# blinky-sch-done.net
KiCad netlist of a schematic drawn in EAGLE
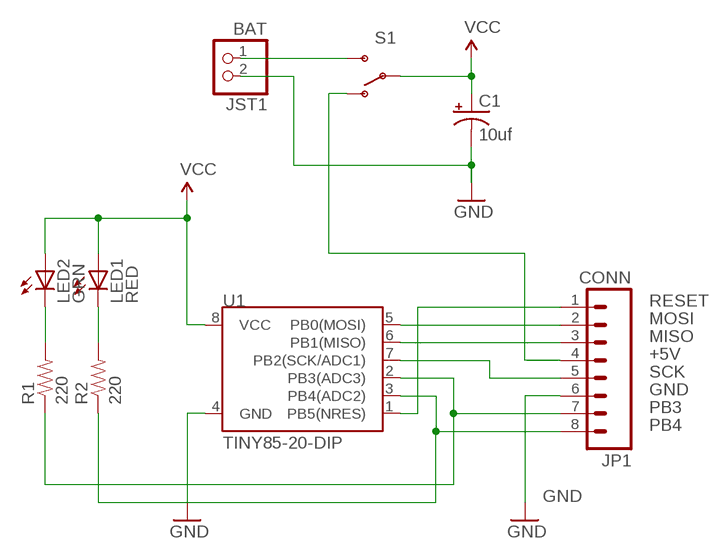
[diagram p0: schematic, sheet 1]

(export (version "E")
  (design (tool "Eeschema 10.0.6"))
  (components
    (comp (ref "C1")
      (value "10uf")
      (footprint "eagle-import:CPOL-RADIAL-10UF-25V")
      (libsource (lib "eagle-import") (part "10UF-25V-20%(PTH)"))
    )
    (comp (ref "JP1")
      (value "CONN")
      (footprint "eagle-import:1X08_LOCK")
      (libsource (lib "eagle-import") (part "M08LOCK"))
    )
    (comp (ref "JST1")
      (value "BAT")
      (footprint "eagle-import:JST-PH-2-THM-RA")
      (libsource (lib "eagle-import") (part "JST_2PIN-THM-RA"))
    )
    (comp (ref "LED1")
      (value "RED")
      (footprint "eagle-import:LED5MM")
      (libsource (lib "eagle-import") (part "LED5MM"))
    )
    (comp (ref "LED2")
      (value "GRN")
      (footprint "eagle-import:LED5MM")
      (libsource (lib "eagle-import") (part "LED5MM"))
    )
    (comp (ref "R1")
      (value "220")
      (footprint "eagle-import:AXIAL-0.3")
      (libsource (lib "eagle-import") (part "RESISTORAXIAL-0.3"))
    )
    (comp (ref "R2")
      (value "220")
      (footprint "eagle-import:AXIAL-0.3")
      (libsource (lib "eagle-import") (part "RESISTORAXIAL-0.3"))
    )
    (comp (ref "S1")
      (value "SWITCH-SPDT")
      (footprint "eagle-import:SWITCH-SPDT_3.2MM")
      (libsource (lib "eagle-import") (part "SWITCH-SPDT"))
    )
    (comp (ref "U1")
      (value "TINY85-20-DIP")
      (footprint "eagle-import:DIP08")
      (libsource (lib "eagle-import") (part "ATTINY85TINY85-20-DIP"))
    )
  )
  (nets
    (net (code "1") (name "/+5V") (class "Default")
      (node (ref "JP1") (pin "4") (pinfunction "4_4") (pintype "passive"))
      (node (ref "S1") (pin "1") (pinfunction "O_1") (pintype "passive"))
    )
    (net (code "2") (name "/MISO") (class "Default")
      (node (ref "JP1") (pin "3") (pinfunction "3_3") (pintype "passive"))
      (node (ref "U1") (pin "6") (pinfunction "PB1(MISO)_6") (pintype "bidirectional"))
    )
    (net (code "3") (name "/MOSI") (class "Default")
      (node (ref "JP1") (pin "2") (pinfunction "2_2") (pintype "passive"))
      (node (ref "U1") (pin "5") (pinfunction "PB0(MOSI)_5") (pintype "bidirectional"))
    )
    (net (code "4") (name "/PB3") (class "Default")
      (node (ref "JP1") (pin "7") (pinfunction "7_7") (pintype "passive"))
      (node (ref "R1") (pin "P$1") (pinfunction "1_P$1") (pintype "passive"))
      (node (ref "U1") (pin "2") (pinfunction "PB3(ADC3)_2") (pintype "bidirectional"))
    )
    (net (code "5") (name "/PB4") (class "Default")
      (node (ref "JP1") (pin "8") (pinfunction "8_8") (pintype "passive"))
      (node (ref "R2") (pin "P$1") (pinfunction "1_P$1") (pintype "passive"))
      (node (ref "U1") (pin "3") (pinfunction "PB4(ADC2)_3") (pintype "bidirectional"))
    )
    (net (code "6") (name "/RESET") (class "Default")
      (node (ref "JP1") (pin "1") (pinfunction "1_1") (pintype "passive"))
      (node (ref "U1") (pin "1") (pinfunction "PB5(NRES)_1") (pintype "bidirectional"))
    )
    (net (code "7") (name "/SCK") (class "Default")
      (node (ref "JP1") (pin "5") (pinfunction "5_5") (pintype "passive"))
      (node (ref "U1") (pin "7") (pinfunction "PB2(SCK/ADC1)_7") (pintype "bidirectional"))
    )
    (net (code "8") (name "GND") (class "Default")
      (node (ref "C1") (pin "2") (pinfunction "-_2") (pintype "passive"))
      (node (ref "JP1") (pin "6") (pinfunction "6_6") (pintype "passive"))
      (node (ref "JST1") (pin "2") (pinfunction "1_2") (pintype "passive"))
      (node (ref "U1") (pin "4") (pinfunction "GND_4") (pintype "bidirectional"))
    )
    (net (code "9") (name "Net-(JST1-2)") (class "Default")
      (node (ref "JST1") (pin "1") (pinfunction "2_1") (pintype "passive"))
      (node (ref "S1") (pin "3") (pinfunction "S_3") (pintype "passive"))
    )
    (net (code "10") (name "Net-(LED1-C)") (class "Default")
      (node (ref "LED1") (pin "K") (pinfunction "C_K") (pintype "passive"))
      (node (ref "R2") (pin "P$2") (pinfunction "2_P$2") (pintype "passive"))
    )
    (net (code "11") (name "Net-(LED2-C)") (class "Default")
      (node (ref "LED2") (pin "K") (pinfunction "C_K") (pintype "passive"))
      (node (ref "R1") (pin "P$2") (pinfunction "2_P$2") (pintype "passive"))
    )
    (net (code "12") (name "VCC") (class "Default")
      (node (ref "C1") (pin "1") (pinfunction "+_1") (pintype "passive"))
      (node (ref "LED1") (pin "A") (pinfunction "A_A") (pintype "passive"))
      (node (ref "LED2") (pin "A") (pinfunction "A_A") (pintype "passive"))
      (node (ref "S1") (pin "2") (pinfunction "P_2") (pintype "passive"))
      (node (ref "U1") (pin "8") (pinfunction "VCC_8") (pintype "bidirectional"))
    )
  )
)
